# Sheet1.net
KiCad netlist of a schematic drawn in Altium Designer
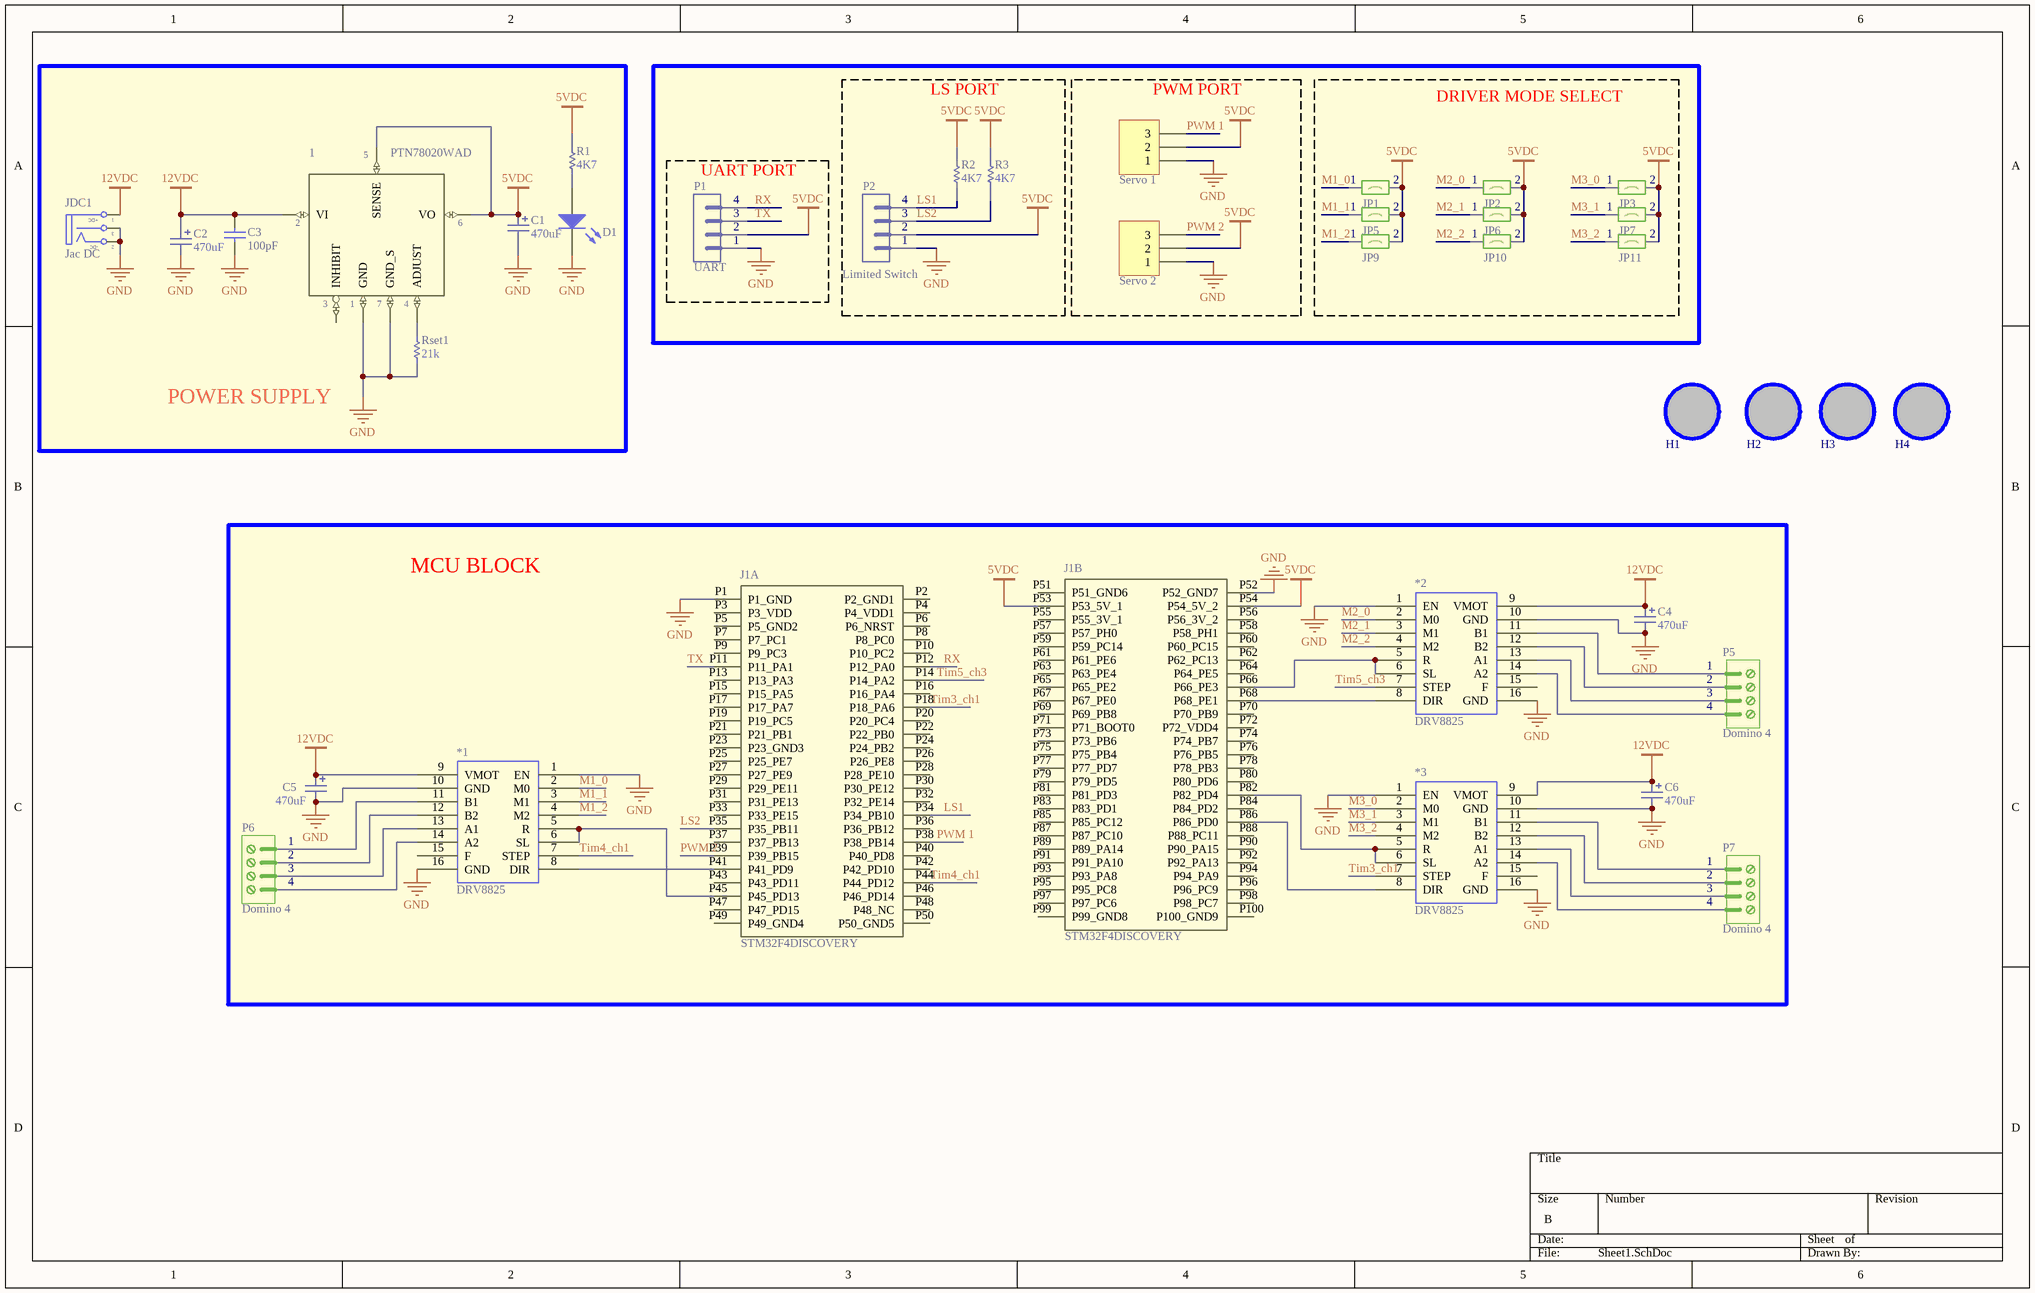
[diagram p0: Sheet1.SchDoc]

(export (version "E")
  (design (tool "Eeschema 10.0.6"))
  (components
    (comp (ref "*1") (value "DRV8825") (footprint "DRV8825") (libsource (lib "DRV8833") (part "DRV8825")))
    (comp (ref "*2") (value "DRV8825") (footprint "DRV8825") (libsource (lib "DRV8833") (part "DRV8825")))
    (comp (ref "*3") (value "DRV8825") (footprint "DRV8825") (libsource (lib "DRV8833") (part "DRV8825")))
    (comp (ref "1")
      (value "PTN78020WAD")
      (footprint "PTN78020WAD")
      (description "6-A Wide-Input Voltage Adjustable Switching egulator 7-Through-Hole Module -40 to 85")
      (fields (field (name "MF") "Texas Instruments"))
      (libsource (lib "PTN78020WAD") (part "PTN78020WAD"))
    )
    (comp (ref "C1")
      (value "470uF")
      (footprint "CP1/2.5")
      (description "Polarized Capacitor (Radial)")
      (fields (field (name "Comment") "Cap Pol"))
      (libsource (lib "minht57_lib") (part "Cap Pol"))
    )
    (comp (ref "C2")
      (value "470uF")
      (footprint "CP1.5/3.4")
      (description "Polarized Capacitor (Radial)")
      (fields (field (name "Comment") "Cap Pol"))
      (libsource (lib "minht57_lib") (part "Cap Pol"))
    )
    (comp (ref "C3")
      (value "100pF")
      (footprint "CAP-SM-0805")
      (description "Capacitor")
      (fields (field (name "Comment") "Cap Non-Pol SMD"))
      (libsource (lib "PIF_Library") (part "Cap Non-Pol SMD"))
    )
    (comp (ref "C4")
      (value "470uF")
      (footprint "CP1/2.5")
      (description "Polarized Capacitor (Radial)")
      (fields (field (name "Comment") "Cap Pol"))
      (libsource (lib "minht57_lib") (part "Cap Pol"))
    )
    (comp (ref "C5")
      (value "470uF")
      (footprint "CP1/2.5")
      (description "Polarized Capacitor (Radial)")
      (fields (field (name "Comment") "Cap Pol"))
      (libsource (lib "minht57_lib") (part "Cap Pol"))
    )
    (comp (ref "C6")
      (value "470uF")
      (footprint "CP1/2.5")
      (description "Polarized Capacitor (Radial)")
      (fields (field (name "Comment") "Cap Pol"))
      (libsource (lib "minht57_lib") (part "Cap Pol"))
    )
    (comp (ref "D1") (value "LED") (footprint "LED-3mm") (libsource (lib "PIF_Library") (part "LED")))
    (comp (ref "H1")
      (value "Hole")
      (footprint "LO KHOAN 3MM")
      (description "Hole 3mm")
      (libsource (lib "PIF_Library") (part "Hole"))
    )
    (comp (ref "H2")
      (value "Hole")
      (footprint "LO KHOAN 3MM")
      (description "Hole 3mm")
      (libsource (lib "PIF_Library") (part "Hole"))
    )
    (comp (ref "H3")
      (value "Hole")
      (footprint "LO KHOAN 3MM")
      (description "Hole 3mm")
      (libsource (lib "PIF_Library") (part "Hole"))
    )
    (comp (ref "H4")
      (value "Hole")
      (footprint "LO KHOAN 3MM")
      (description "Hole 3mm")
      (libsource (lib "PIF_Library") (part "Hole"))
    )
    (comp (ref "J1")
      (value "STM32F4DISCOVERY")
      (footprint "STMICROELECTRONICS_STM32F4DISCOVERY_STM32F4DISCOVERY(Primary)")
      (description "Development kit: ARM ST; pin strips, pin header; No.of")
      (fields (field (name "MF") "STMicroelectronics"))
      (libsource (lib "STM32F4DISCOVERY") (part "STM32F4DISCOVERY"))
    )
    (comp (ref "JDC1")
      (value "Jac DC")
      (footprint "DC-IN")
      (description "Jac DC input")
      (libsource (lib "syhaunguyen(1)") (part "DCIN"))
    )
    (comp (ref "JP1") (value "Jumper 2") (footprint "JP2") (libsource (lib "minht57_lib") (part "Jumper 2")))
    (comp (ref "JP2") (value "Jumper 2") (footprint "JP2") (libsource (lib "minht57_lib") (part "Jumper 2")))
    (comp (ref "JP3") (value "Jumper 2") (footprint "JP2") (libsource (lib "minht57_lib") (part "Jumper 2")))
    (comp (ref "JP5") (value "Jumper 2") (footprint "JP2") (libsource (lib "minht57_lib") (part "Jumper 2")))
    (comp (ref "JP6") (value "Jumper 2") (footprint "JP2") (libsource (lib "minht57_lib") (part "Jumper 2")))
    (comp (ref "JP7") (value "Jumper 2") (footprint "JP2") (libsource (lib "minht57_lib") (part "Jumper 2")))
    (comp (ref "JP9") (value "Jumper 2") (footprint "JP2") (libsource (lib "minht57_lib") (part "Jumper 2")))
    (comp (ref "JP10") (value "Jumper 2") (footprint "JP2") (libsource (lib "minht57_lib") (part "Jumper 2")))
    (comp (ref "JP11") (value "Jumper 2") (footprint "JP2") (libsource (lib "minht57_lib") (part "Jumper 2")))
    (comp (ref "P1")
      (value "UART")
      (footprint "JP4")
      (description "Header, 4-Pin")
      (fields (field (name "PUBLISHER") "Altium Limited"))
      (libsource (lib "minht57_lib") (part "Header 4"))
    )
    (comp (ref "P2")
      (value "Limited Switch")
      (footprint "JP4")
      (description "Header, 4-Pin")
      (fields (field (name "PUBLISHER") "Altium Limited"))
      (libsource (lib "minht57_lib") (part "Header 4"))
    )
    (comp (ref "P5")
      (value "Domino 4")
      (footprint "DOMINO 4 -5mm")
      (description "Domino 4-Pin")
      (fields (field (name "PUBLISHER") "Altium Limited"))
      (libsource (lib "minht57_lib") (part "Domino 4"))
    )
    (comp (ref "P6")
      (value "Domino 4")
      (footprint "DOMINO 4 -5mm")
      (description "Domino 4-Pin")
      (fields (field (name "PUBLISHER") "Altium Limited"))
      (libsource (lib "") (part "Domino 4_1"))
    )
    (comp (ref "P7")
      (value "Domino 4")
      (footprint "DOMINO 4 -5mm")
      (description "Domino 4-Pin")
      (fields (field (name "PUBLISHER") "Altium Limited"))
      (libsource (lib "minht57_lib") (part "Domino 4"))
    )
    (comp (ref "R1")
      (value "4K7")
      (footprint "RES-SM-0805")
      (description "Resistor")
      (fields (field (name "Comment") "Res SMD"))
      (libsource (lib "minht57_lib") (part "Res SMD"))
    )
    (comp (ref "R2")
      (value "4K7")
      (footprint "RES-SM-0805")
      (description "Resistor")
      (fields (field (name "Comment") "Res SMD"))
      (libsource (lib "minht57_lib") (part "Res SMD"))
    )
    (comp (ref "R3")
      (value "4K7")
      (footprint "RES-SM-0805")
      (description "Resistor")
      (fields (field (name "Comment") "Res SMD"))
      (libsource (lib "minht57_lib") (part "Res SMD"))
    )
    (comp (ref "Rset1")
      (value "Res SMD")
      (footprint "RES-SM-0805")
      (description "Resistor")
      (fields (field (name "1%") "21k"))
      (libsource (lib "minht57_lib") (part "Res SMD"))
    )
    (comp (ref "Servo 1")
      (value "Header 3")
      (footprint "JP3")
      (description "Header, 3-Pin")
      (fields (field (name "PUBLISHER") "Altium Limited"))
      (libsource (lib "PIF_Library") (part "Header 3"))
    )
    (comp (ref "Servo 2")
      (value "Header 3")
      (footprint "JP3")
      (description "Header, 3-Pin")
      (fields (field (name "PUBLISHER") "Altium Limited"))
      (libsource (lib "PIF_Library") (part "Header 3"))
    )
  )
  (nets
    (net (code "1") (name "/LS1") (class "Default")
      (node (ref "J1") (pin "P34") (pinfunction "P34_PB10_P34") (pintype "passive"))
      (node (ref "P2") (pin "4") (pinfunction "4_4") (pintype "passive"))
      (node (ref "R2") (pin "1") (pinfunction "1_1") (pintype "passive"))
    )
    (net (code "2") (name "/LS2") (class "Default")
      (node (ref "J1") (pin "P35") (pinfunction "P35_PB11_P35") (pintype "passive"))
      (node (ref "P2") (pin "3") (pinfunction "3_3") (pintype "passive"))
      (node (ref "R3") (pin "1") (pinfunction "1_1") (pintype "passive"))
    )
    (net (code "3") (name "/M1_0") (class "Default")
      (node (ref "*1") (pin "2") (pinfunction "M0_2") (pintype "passive"))
      (node (ref "JP1") (pin "1") (pinfunction "1_1") (pintype "passive"))
    )
    (net (code "4") (name "/M1_1") (class "Default")
      (node (ref "*1") (pin "3") (pinfunction "M1_3") (pintype "passive"))
      (node (ref "JP5") (pin "1") (pinfunction "1_1") (pintype "passive"))
    )
    (net (code "5") (name "/M1_2") (class "Default")
      (node (ref "*1") (pin "4") (pinfunction "M2_4") (pintype "passive"))
      (node (ref "JP9") (pin "1") (pinfunction "1_1") (pintype "passive"))
    )
    (net (code "6") (name "/M2_0") (class "Default")
      (node (ref "*2") (pin "2") (pinfunction "M0_2") (pintype "passive"))
      (node (ref "JP2") (pin "1") (pinfunction "1_1") (pintype "passive"))
    )
    (net (code "7") (name "/M2_1") (class "Default")
      (node (ref "*2") (pin "3") (pinfunction "M1_3") (pintype "passive"))
      (node (ref "JP6") (pin "1") (pinfunction "1_1") (pintype "passive"))
    )
    (net (code "8") (name "/M2_2") (class "Default")
      (node (ref "*2") (pin "4") (pinfunction "M2_4") (pintype "passive"))
      (node (ref "JP10") (pin "1") (pinfunction "1_1") (pintype "passive"))
    )
    (net (code "9") (name "/M3_0") (class "Default")
      (node (ref "*3") (pin "2") (pinfunction "M0_2") (pintype "passive"))
      (node (ref "JP3") (pin "1") (pinfunction "1_1") (pintype "passive"))
    )
    (net (code "10") (name "/M3_1") (class "Default")
      (node (ref "*3") (pin "3") (pinfunction "M1_3") (pintype "passive"))
      (node (ref "JP7") (pin "1") (pinfunction "1_1") (pintype "passive"))
    )
    (net (code "11") (name "/M3_2") (class "Default")
      (node (ref "*3") (pin "4") (pinfunction "M2_4") (pintype "passive"))
      (node (ref "JP11") (pin "1") (pinfunction "1_1") (pintype "passive"))
    )
    (net (code "12") (name "/PWM 1") (class "Default")
      (node (ref "J1") (pin "P38") (pinfunction "P38_PB14_P38") (pintype "passive"))
      (node (ref "Servo 1") (pin "3") (pinfunction "3_3") (pintype "passive"))
    )
    (net (code "13") (name "/PWM 2") (class "Default")
      (node (ref "J1") (pin "P39") (pinfunction "P39_PB15_P39") (pintype "passive"))
      (node (ref "Servo 2") (pin "3") (pinfunction "3_3") (pintype "passive"))
    )
    (net (code "14") (name "/RX") (class "Default")
      (node (ref "J1") (pin "P12") (pinfunction "P12_PA0_P12") (pintype "passive"))
      (node (ref "P1") (pin "4") (pinfunction "4_4") (pintype "passive"))
    )
    (net (code "15") (name "/TX") (class "Default")
      (node (ref "J1") (pin "P11") (pinfunction "P11_PA1_P11") (pintype "passive"))
      (node (ref "P1") (pin "3") (pinfunction "3_3") (pintype "passive"))
    )
    (net (code "16") (name "/Tim3_ch1") (class "Default")
      (node (ref "*3") (pin "7") (pinfunction "STEP_7") (pintype "passive"))
      (node (ref "J1") (pin "P18") (pinfunction "P18_PA6_P18") (pintype "passive"))
    )
    (net (code "17") (name "/Tim4_ch1") (class "Default")
      (node (ref "*1") (pin "7") (pinfunction "STEP_7") (pintype "passive"))
      (node (ref "J1") (pin "P44") (pinfunction "P44_PD12_P44") (pintype "passive"))
    )
    (net (code "18") (name "/Tim5_ch3") (class "Default")
      (node (ref "*2") (pin "7") (pinfunction "STEP_7") (pintype "passive"))
      (node (ref "J1") (pin "P14") (pinfunction "P14_PA2_P14") (pintype "passive"))
    )
    (net (code "19") (name "5VDC") (class "Default")
      (node (ref "1") (pin "5") (pinfunction "SENSE_5") (pintype "bidirectional"))
      (node (ref "1") (pin "6") (pinfunction "VO_6") (pintype "bidirectional"))
      (node (ref "C1") (pin "1") (pinfunction "1_1") (pintype "passive"))
      (node (ref "J1") (pin "P53") (pinfunction "P53_5V_1_P53") (pintype "passive"))
      (node (ref "J1") (pin "P54") (pinfunction "P54_5V_2_P54") (pintype "passive"))
      (node (ref "JP1") (pin "2") (pinfunction "2_2") (pintype "passive"))
      (node (ref "JP10") (pin "2") (pinfunction "2_2") (pintype "passive"))
      (node (ref "JP11") (pin "2") (pinfunction "2_2") (pintype "passive"))
      (node (ref "JP2") (pin "2") (pinfunction "2_2") (pintype "passive"))
      (node (ref "JP3") (pin "2") (pinfunction "2_2") (pintype "passive"))
      (node (ref "JP5") (pin "2") (pinfunction "2_2") (pintype "passive"))
      (node (ref "JP6") (pin "2") (pinfunction "2_2") (pintype "passive"))
      (node (ref "JP7") (pin "2") (pinfunction "2_2") (pintype "passive"))
      (node (ref "JP9") (pin "2") (pinfunction "2_2") (pintype "passive"))
      (node (ref "P1") (pin "2") (pinfunction "2_2") (pintype "passive"))
      (node (ref "P2") (pin "2") (pinfunction "2_2") (pintype "passive"))
      (node (ref "R1") (pin "2") (pinfunction "2_2") (pintype "passive"))
      (node (ref "R2") (pin "2") (pinfunction "2_2") (pintype "passive"))
      (node (ref "R3") (pin "2") (pinfunction "2_2") (pintype "passive"))
      (node (ref "Servo 1") (pin "2") (pinfunction "2_2") (pintype "passive"))
      (node (ref "Servo 2") (pin "2") (pinfunction "2_2") (pintype "passive"))
    )
    (net (code "20") (name "12VDC") (class "Default")
      (node (ref "*1") (pin "9") (pinfunction "VMOT_9") (pintype "passive"))
      (node (ref "*2") (pin "9") (pinfunction "VMOT_9") (pintype "passive"))
      (node (ref "*3") (pin "9") (pinfunction "VMOT_9") (pintype "passive"))
      (node (ref "1") (pin "2") (pinfunction "VI_2") (pintype "bidirectional"))
      (node (ref "C2") (pin "1") (pinfunction "1_1") (pintype "passive"))
      (node (ref "C3") (pin "2") (pinfunction "2_2") (pintype "passive"))
      (node (ref "C4") (pin "1") (pinfunction "1_1") (pintype "passive"))
      (node (ref "C5") (pin "1") (pinfunction "1_1") (pintype "passive"))
      (node (ref "C6") (pin "1") (pinfunction "1_1") (pintype "passive"))
      (node (ref "JDC1") (pin "1") (pinfunction "T_1") (pintype "passive"))
    )
    (net (code "21") (name "GND") (class "Default")
      (node (ref "*1") (pin "1") (pinfunction "EN_1") (pintype "passive"))
      (node (ref "*1") (pin "10") (pinfunction "GND_10") (pintype "passive"))
      (node (ref "*1") (pin "16") (pinfunction "GND_16") (pintype "passive"))
      (node (ref "*2") (pin "1") (pinfunction "EN_1") (pintype "passive"))
      (node (ref "*2") (pin "10") (pinfunction "GND_10") (pintype "passive"))
      (node (ref "*2") (pin "16") (pinfunction "GND_16") (pintype "passive"))
      (node (ref "*3") (pin "1") (pinfunction "EN_1") (pintype "passive"))
      (node (ref "*3") (pin "10") (pinfunction "GND_10") (pintype "passive"))
      (node (ref "*3") (pin "16") (pinfunction "GND_16") (pintype "passive"))
      (node (ref "1") (pin "1") (pinfunction "GND_1") (pintype "bidirectional"))
      (node (ref "1") (pin "7") (pinfunction "GND_S_7") (pintype "bidirectional"))
      (node (ref "C1") (pin "2") (pinfunction "2_2") (pintype "passive"))
      (node (ref "C2") (pin "2") (pinfunction "2_2") (pintype "passive"))
      (node (ref "C3") (pin "1") (pinfunction "1_1") (pintype "passive"))
      (node (ref "C4") (pin "2") (pinfunction "2_2") (pintype "passive"))
      (node (ref "C5") (pin "2") (pinfunction "2_2") (pintype "passive"))
      (node (ref "C6") (pin "2") (pinfunction "2_2") (pintype "passive"))
      (node (ref "D1") (pin "2") (pinfunction "K_2") (pintype "passive"))
      (node (ref "J1") (pin "P1") (pinfunction "P1_GND_P1") (pintype "passive"))
      (node (ref "J1") (pin "P52") (pinfunction "P52_GND7_P52") (pintype "passive"))
      (node (ref "JDC1") (pin "2") (pinfunction "TN_2") (pintype "passive"))
      (node (ref "JDC1") (pin "3") (pinfunction "S_3") (pintype "power_in"))
      (node (ref "P1") (pin "1") (pinfunction "1_1") (pintype "passive"))
      (node (ref "P2") (pin "1") (pinfunction "1_1") (pintype "passive"))
      (node (ref "Rset1") (pin "1") (pinfunction "1_1") (pintype "passive"))
      (node (ref "Servo 1") (pin "1") (pinfunction "1_1") (pintype "passive"))
      (node (ref "Servo 2") (pin "1") (pinfunction "1_1") (pintype "passive"))
    )
    (net (code "22") (name "Net-(*1-A1)") (class "Default")
      (node (ref "*1") (pin "13") (pinfunction "A1_13") (pintype "passive"))
      (node (ref "P6") (pin "3") (pinfunction "3_3") (pintype "passive"))
    )
    (net (code "23") (name "Net-(*1-A2)") (class "Default")
      (node (ref "*1") (pin "14") (pinfunction "A2_14") (pintype "passive"))
      (node (ref "P6") (pin "4") (pinfunction "4_4") (pintype "passive"))
    )
    (net (code "24") (name "Net-(*1-B1)") (class "Default")
      (node (ref "*1") (pin "11") (pinfunction "B1_11") (pintype "passive"))
      (node (ref "P6") (pin "1") (pinfunction "1_1") (pintype "passive"))
    )
    (net (code "25") (name "Net-(*1-B2)") (class "Default")
      (node (ref "*1") (pin "12") (pinfunction "B2_12") (pintype "passive"))
      (node (ref "P6") (pin "2") (pinfunction "2_2") (pintype "passive"))
    )
    (net (code "26") (name "Net-(*1-DIR)") (class "Default")
      (node (ref "*1") (pin "8") (pinfunction "DIR_8") (pintype "passive"))
      (node (ref "J1") (pin "P41") (pinfunction "P41_PD9_P41") (pintype "passive"))
    )
    (net (code "27") (name "Net-(*1-R)") (class "Default")
      (node (ref "*1") (pin "5") (pinfunction "R_5") (pintype "passive"))
      (node (ref "*1") (pin "6") (pinfunction "SL_6") (pintype "passive"))
      (node (ref "J1") (pin "P45") (pinfunction "P45_PD13_P45") (pintype "passive"))
    )
    (net (code "28") (name "Net-(*2-A1)") (class "Default")
      (node (ref "*2") (pin "13") (pinfunction "A1_13") (pintype "passive"))
      (node (ref "P5") (pin "3") (pinfunction "3_3") (pintype "passive"))
    )
    (net (code "29") (name "Net-(*2-A2)") (class "Default")
      (node (ref "*2") (pin "14") (pinfunction "A2_14") (pintype "passive"))
      (node (ref "P5") (pin "4") (pinfunction "4_4") (pintype "passive"))
    )
    (net (code "30") (name "Net-(*2-B1)") (class "Default")
      (node (ref "*2") (pin "11") (pinfunction "B1_11") (pintype "passive"))
      (node (ref "P5") (pin "1") (pinfunction "1_1") (pintype "passive"))
    )
    (net (code "31") (name "Net-(*2-B2)") (class "Default")
      (node (ref "*2") (pin "12") (pinfunction "B2_12") (pintype "passive"))
      (node (ref "P5") (pin "2") (pinfunction "2_2") (pintype "passive"))
    )
    (net (code "32") (name "Net-(*2-DIR)") (class "Default")
      (node (ref "*2") (pin "8") (pinfunction "DIR_8") (pintype "passive"))
      (node (ref "J1") (pin "P68") (pinfunction "P68_PE1_P68") (pintype "passive"))
    )
    (net (code "33") (name "Net-(*2-R)") (class "Default")
      (node (ref "*2") (pin "5") (pinfunction "R_5") (pintype "passive"))
      (node (ref "*2") (pin "6") (pinfunction "SL_6") (pintype "passive"))
      (node (ref "J1") (pin "P66") (pinfunction "P66_PE3_P66") (pintype "passive"))
    )
    (net (code "34") (name "Net-(*3-A1)") (class "Default")
      (node (ref "*3") (pin "13") (pinfunction "A1_13") (pintype "passive"))
      (node (ref "P7") (pin "3") (pinfunction "3_3") (pintype "passive"))
    )
    (net (code "35") (name "Net-(*3-A2)") (class "Default")
      (node (ref "*3") (pin "14") (pinfunction "A2_14") (pintype "passive"))
      (node (ref "P7") (pin "4") (pinfunction "4_4") (pintype "passive"))
    )
    (net (code "36") (name "Net-(*3-B1)") (class "Default")
      (node (ref "*3") (pin "11") (pinfunction "B1_11") (pintype "passive"))
      (node (ref "P7") (pin "1") (pinfunction "1_1") (pintype "passive"))
    )
    (net (code "37") (name "Net-(*3-B2)") (class "Default")
      (node (ref "*3") (pin "12") (pinfunction "B2_12") (pintype "passive"))
      (node (ref "P7") (pin "2") (pinfunction "2_2") (pintype "passive"))
    )
    (net (code "38") (name "Net-(*3-DIR)") (class "Default")
      (node (ref "*3") (pin "8") (pinfunction "DIR_8") (pintype "passive"))
      (node (ref "J1") (pin "P86") (pinfunction "P86_PD0_P86") (pintype "passive"))
    )
    (net (code "39") (name "Net-(*3-R)") (class "Default")
      (node (ref "*3") (pin "5") (pinfunction "R_5") (pintype "passive"))
      (node (ref "*3") (pin "6") (pinfunction "SL_6") (pintype "passive"))
      (node (ref "J1") (pin "P82") (pinfunction "P82_PD4_P82") (pintype "passive"))
    )
    (net (code "40") (name "Net-(1-ADJUST)") (class "Default")
      (node (ref "1") (pin "4") (pinfunction "ADJUST_4") (pintype "bidirectional"))
      (node (ref "Rset1") (pin "2") (pinfunction "2_2") (pintype "passive"))
    )
    (net (code "41") (name "Net-(D1-A)") (class "Default")
      (node (ref "D1") (pin "1") (pinfunction "A_1") (pintype "passive"))
      (node (ref "R1") (pin "1") (pinfunction "1_1") (pintype "passive"))
    )
    (net (code "42") (name "unconnected-(*1-F-Pad15)") (class "Default")
      (node (ref "*1") (pin "15") (pinfunction "F_15") (pintype "passive"))
    )
    (net (code "43") (name "unconnected-(*2-F-Pad15)") (class "Default")
      (node (ref "*2") (pin "15") (pinfunction "F_15") (pintype "passive"))
    )
    (net (code "44") (name "unconnected-(*3-F-Pad15)") (class "Default")
      (node (ref "*3") (pin "15") (pinfunction "F_15") (pintype "passive"))
    )
    (net (code "45") (name "unconnected-(1-INHIBIT-Pad3)") (class "Default")
      (node (ref "1") (pin "3") (pinfunction "INHIBIT_3") (pintype "bidirectional"))
    )
    (net (code "46") (name "unconnected-(H1-Pad1)") (class "Default")
      (node (ref "H1") (pin "1") (pinfunction "1_1") (pintype "passive"))
    )
    (net (code "47") (name "unconnected-(H2-Pad1)") (class "Default")
      (node (ref "H2") (pin "1") (pinfunction "1_1") (pintype "passive"))
    )
    (net (code "48") (name "unconnected-(H3-Pad1)") (class "Default")
      (node (ref "H3") (pin "1") (pinfunction "1_1") (pintype "passive"))
    )
    (net (code "49") (name "unconnected-(H4-Pad1)") (class "Default")
      (node (ref "H4") (pin "1") (pinfunction "1_1") (pintype "passive"))
    )
    (net (code "50") (name "unconnected-(J1A-P2_GND1-PadP2)") (class "Default")
      (node (ref "J1") (pin "P2") (pinfunction "P2_GND1_P2") (pintype "passive"))
    )
    (net (code "51") (name "unconnected-(J1A-P3_VDD-PadP3)") (class "Default")
      (node (ref "J1") (pin "P3") (pinfunction "P3_VDD_P3") (pintype "passive"))
    )
    (net (code "52") (name "unconnected-(J1A-P4_VDD1-PadP4)") (class "Default")
      (node (ref "J1") (pin "P4") (pinfunction "P4_VDD1_P4") (pintype "passive"))
    )
    (net (code "53") (name "unconnected-(J1A-P5_GND2-PadP5)") (class "Default")
      (node (ref "J1") (pin "P5") (pinfunction "P5_GND2_P5") (pintype "passive"))
    )
    (net (code "54") (name "unconnected-(J1A-P6_NRST-PadP6)") (class "Default")
      (node (ref "J1") (pin "P6") (pinfunction "P6_NRST_P6") (pintype "passive"))
    )
    (net (code "55") (name "unconnected-(J1A-P7_PC1-PadP7)") (class "Default")
      (node (ref "J1") (pin "P7") (pinfunction "P7_PC1_P7") (pintype "passive"))
    )
    (net (code "56") (name "unconnected-(J1A-P8_PC0-PadP8)") (class "Default")
      (node (ref "J1") (pin "P8") (pinfunction "P8_PC0_P8") (pintype "passive"))
    )
    (net (code "57") (name "unconnected-(J1A-P9_PC3-PadP9)") (class "Default")
      (node (ref "J1") (pin "P9") (pinfunction "P9_PC3_P9") (pintype "passive"))
    )
    (net (code "58") (name "unconnected-(J1A-P10_PC2-PadP10)") (class "Default")
      (node (ref "J1") (pin "P10") (pinfunction "P10_PC2_P10") (pintype "passive"))
    )
    (net (code "59") (name "unconnected-(J1A-P13_PA3-PadP13)") (class "Default")
      (node (ref "J1") (pin "P13") (pinfunction "P13_PA3_P13") (pintype "passive"))
    )
    (net (code "60") (name "unconnected-(J1A-P15_PA5-PadP15)") (class "Default")
      (node (ref "J1") (pin "P15") (pinfunction "P15_PA5_P15") (pintype "passive"))
    )
    (net (code "61") (name "unconnected-(J1A-P16_PA4-PadP16)") (class "Default")
      (node (ref "J1") (pin "P16") (pinfunction "P16_PA4_P16") (pintype "passive"))
    )
    (net (code "62") (name "unconnected-(J1A-P17_PA7-PadP17)") (class "Default")
      (node (ref "J1") (pin "P17") (pinfunction "P17_PA7_P17") (pintype "passive"))
    )
    (net (code "63") (name "unconnected-(J1A-P19_PC5-PadP19)") (class "Default")
      (node (ref "J1") (pin "P19") (pinfunction "P19_PC5_P19") (pintype "passive"))
    )
    (net (code "64") (name "unconnected-(J1A-P20_PC4-PadP20)") (class "Default")
      (node (ref "J1") (pin "P20") (pinfunction "P20_PC4_P20") (pintype "passive"))
    )
    (net (code "65") (name "unconnected-(J1A-P21_PB1-PadP21)") (class "Default")
      (node (ref "J1") (pin "P21") (pinfunction "P21_PB1_P21") (pintype "passive"))
    )
    (net (code "66") (name "unconnected-(J1A-P22_PB0-PadP22)") (class "Default")
      (node (ref "J1") (pin "P22") (pinfunction "P22_PB0_P22") (pintype "passive"))
    )
    (net (code "67") (name "unconnected-(J1A-P23_GND3-PadP23)") (class "Default")
      (node (ref "J1") (pin "P23") (pinfunction "P23_GND3_P23") (pintype "passive"))
    )
    (net (code "68") (name "unconnected-(J1A-P24_PB2-PadP24)") (class "Default")
      (node (ref "J1") (pin "P24") (pinfunction "P24_PB2_P24") (pintype "passive"))
    )
    (net (code "69") (name "unconnected-(J1A-P25_PE7-PadP25)") (class "Default")
      (node (ref "J1") (pin "P25") (pinfunction "P25_PE7_P25") (pintype "passive"))
    )
    (net (code "70") (name "unconnected-(J1A-P26_PE8-PadP26)") (class "Default")
      (node (ref "J1") (pin "P26") (pinfunction "P26_PE8_P26") (pintype "passive"))
    )
    (net (code "71") (name "unconnected-(J1A-P27_PE9-PadP27)") (class "Default")
      (node (ref "J1") (pin "P27") (pinfunction "P27_PE9_P27") (pintype "passive"))
    )
    (net (code "72") (name "unconnected-(J1A-P28_PE10-PadP28)") (class "Default")
      (node (ref "J1") (pin "P28") (pinfunction "P28_PE10_P28") (pintype "passive"))
    )
    (net (code "73") (name "unconnected-(J1A-P29_PE11-PadP29)") (class "Default")
      (node (ref "J1") (pin "P29") (pinfunction "P29_PE11_P29") (pintype "passive"))
    )
    (net (code "74") (name "unconnected-(J1A-P30_PE12-PadP30)") (class "Default")
      (node (ref "J1") (pin "P30") (pinfunction "P30_PE12_P30") (pintype "passive"))
    )
    (net (code "75") (name "unconnected-(J1A-P31_PE13-PadP31)") (class "Default")
      (node (ref "J1") (pin "P31") (pinfunction "P31_PE13_P31") (pintype "passive"))
    )
    (net (code "76") (name "unconnected-(J1A-P32_PE14-PadP32)") (class "Default")
      (node (ref "J1") (pin "P32") (pinfunction "P32_PE14_P32") (pintype "passive"))
    )
    (net (code "77") (name "unconnected-(J1A-P33_PE15-PadP33)") (class "Default")
      (node (ref "J1") (pin "P33") (pinfunction "P33_PE15_P33") (pintype "passive"))
    )
    (net (code "78") (name "unconnected-(J1A-P36_PB12-PadP36)") (class "Default")
      (node (ref "J1") (pin "P36") (pinfunction "P36_PB12_P36") (pintype "passive"))
    )
    (net (code "79") (name "unconnected-(J1A-P37_PB13-PadP37)") (class "Default")
      (node (ref "J1") (pin "P37") (pinfunction "P37_PB13_P37") (pintype "passive"))
    )
    (net (code "80") (name "unconnected-(J1A-P40_PD8-PadP40)") (class "Default")
      (node (ref "J1") (pin "P40") (pinfunction "P40_PD8_P40") (pintype "passive"))
    )
    (net (code "81") (name "unconnected-(J1A-P42_PD10-PadP42)") (class "Default")
      (node (ref "J1") (pin "P42") (pinfunction "P42_PD10_P42") (pintype "passive"))
    )
    (net (code "82") (name "unconnected-(J1A-P43_PD11-PadP43)") (class "Default")
      (node (ref "J1") (pin "P43") (pinfunction "P43_PD11_P43") (pintype "passive"))
    )
    (net (code "83") (name "unconnected-(J1A-P46_PD14-PadP46)") (class "Default")
      (node (ref "J1") (pin "P46") (pinfunction "P46_PD14_P46") (pintype "passive"))
    )
    (net (code "84") (name "unconnected-(J1A-P47_PD15-PadP47)") (class "Default")
      (node (ref "J1") (pin "P47") (pinfunction "P47_PD15_P47") (pintype "passive"))
    )
    (net (code "85") (name "unconnected-(J1A-P48_NC-PadP48)") (class "Default")
      (node (ref "J1") (pin "P48") (pinfunction "P48_NC_P48") (pintype "passive"))
    )
    (net (code "86") (name "unconnected-(J1A-P49_GND4-PadP49)") (class "Default")
      (node (ref "J1") (pin "P49") (pinfunction "P49_GND4_P49") (pintype "passive"))
    )
    (net (code "87") (name "unconnected-(J1A-P50_GND5-PadP50)") (class "Default")
      (node (ref "J1") (pin "P50") (pinfunction "P50_GND5_P50") (pintype "passive"))
    )
    (net (code "88") (name "unconnected-(J1B-P51_GND6-PadP51)") (class "Default")
      (node (ref "J1") (pin "P51") (pinfunction "P51_GND6_P51") (pintype "passive"))
    )
    (net (code "89") (name "unconnected-(J1B-P55_3V_1-PadP55)") (class "Default")
      (node (ref "J1") (pin "P55") (pinfunction "P55_3V_1_P55") (pintype "passive"))
    )
    (net (code "90") (name "unconnected-(J1B-P56_3V_2-PadP56)") (class "Default")
      (node (ref "J1") (pin "P56") (pinfunction "P56_3V_2_P56") (pintype "passive"))
    )
    (net (code "91") (name "unconnected-(J1B-P57_PH0-PadP57)") (class "Default")
      (node (ref "J1") (pin "P57") (pinfunction "P57_PH0_P57") (pintype "passive"))
    )
    (net (code "92") (name "unconnected-(J1B-P58_PH1-PadP58)") (class "Default")
      (node (ref "J1") (pin "P58") (pinfunction "P58_PH1_P58") (pintype "passive"))
    )
    (net (code "93") (name "unconnected-(J1B-P59_PC14-PadP59)") (class "Default")
      (node (ref "J1") (pin "P59") (pinfunction "P59_PC14_P59") (pintype "passive"))
    )
    (net (code "94") (name "unconnected-(J1B-P60_PC15-PadP60)") (class "Default")
      (node (ref "J1") (pin "P60") (pinfunction "P60_PC15_P60") (pintype "passive"))
    )
    (net (code "95") (name "unconnected-(J1B-P61_PE6-PadP61)") (class "Default")
      (node (ref "J1") (pin "P61") (pinfunction "P61_PE6_P61") (pintype "passive"))
    )
    (net (code "96") (name "unconnected-(J1B-P62_PC13-PadP62)") (class "Default")
      (node (ref "J1") (pin "P62") (pinfunction "P62_PC13_P62") (pintype "passive"))
    )
    (net (code "97") (name "unconnected-(J1B-P63_PE4-PadP63)") (class "Default")
      (node (ref "J1") (pin "P63") (pinfunction "P63_PE4_P63") (pintype "passive"))
    )
    (net (code "98") (name "unconnected-(J1B-P64_PE5-PadP64)") (class "Default")
      (node (ref "J1") (pin "P64") (pinfunction "P64_PE5_P64") (pintype "passive"))
    )
    (net (code "99") (name "unconnected-(J1B-P65_PE2-PadP65)") (class "Default")
      (node (ref "J1") (pin "P65") (pinfunction "P65_PE2_P65") (pintype "passive"))
    )
    (net (code "100") (name "unconnected-(J1B-P67_PE0-PadP67)") (class "Default")
      (node (ref "J1") (pin "P67") (pinfunction "P67_PE0_P67") (pintype "passive"))
    )
    (net (code "101") (name "unconnected-(J1B-P69_PB8-PadP69)") (class "Default")
      (node (ref "J1") (pin "P69") (pinfunction "P69_PB8_P69") (pintype "passive"))
    )
    (net (code "102") (name "unconnected-(J1B-P70_PB9-PadP70)") (class "Default")
      (node (ref "J1") (pin "P70") (pinfunction "P70_PB9_P70") (pintype "passive"))
    )
    (net (code "103") (name "unconnected-(J1B-P71_BOOT0-PadP71)") (class "Default")
      (node (ref "J1") (pin "P71") (pinfunction "P71_BOOT0_P71") (pintype "passive"))
    )
    (net (code "104") (name "unconnected-(J1B-P72_VDD4-PadP72)") (class "Default")
      (node (ref "J1") (pin "P72") (pinfunction "P72_VDD4_P72") (pintype "passive"))
    )
    (net (code "105") (name "unconnected-(J1B-P73_PB6-PadP73)") (class "Default")
      (node (ref "J1") (pin "P73") (pinfunction "P73_PB6_P73") (pintype "passive"))
    )
    (net (code "106") (name "unconnected-(J1B-P74_PB7-PadP74)") (class "Default")
      (node (ref "J1") (pin "P74") (pinfunction "P74_PB7_P74") (pintype "passive"))
    )
    (net (code "107") (name "unconnected-(J1B-P75_PB4-PadP75)") (class "Default")
      (node (ref "J1") (pin "P75") (pinfunction "P75_PB4_P75") (pintype "passive"))
    )
    (net (code "108") (name "unconnected-(J1B-P76_PB5-PadP76)") (class "Default")
      (node (ref "J1") (pin "P76") (pinfunction "P76_PB5_P76") (pintype "passive"))
    )
    (net (code "109") (name "unconnected-(J1B-P77_PD7-PadP77)") (class "Default")
      (node (ref "J1") (pin "P77") (pinfunction "P77_PD7_P77") (pintype "passive"))
    )
    (net (code "110") (name "unconnected-(J1B-P78_PB3-PadP78)") (class "Default")
      (node (ref "J1") (pin "P78") (pinfunction "P78_PB3_P78") (pintype "passive"))
    )
    (net (code "111") (name "unconnected-(J1B-P79_PD5-PadP79)") (class "Default")
      (node (ref "J1") (pin "P79") (pinfunction "P79_PD5_P79") (pintype "passive"))
    )
    (net (code "112") (name "unconnected-(J1B-P80_PD6-PadP80)") (class "Default")
      (node (ref "J1") (pin "P80") (pinfunction "P80_PD6_P80") (pintype "passive"))
    )
    (net (code "113") (name "unconnected-(J1B-P81_PD3-PadP81)") (class "Default")
      (node (ref "J1") (pin "P81") (pinfunction "P81_PD3_P81") (pintype "passive"))
    )
    (net (code "114") (name "unconnected-(J1B-P83_PD1-PadP83)") (class "Default")
      (node (ref "J1") (pin "P83") (pinfunction "P83_PD1_P83") (pintype "passive"))
    )
    (net (code "115") (name "unconnected-(J1B-P84_PD2-PadP84)") (class "Default")
      (node (ref "J1") (pin "P84") (pinfunction "P84_PD2_P84") (pintype "passive"))
    )
    (net (code "116") (name "unconnected-(J1B-P85_PC12-PadP85)") (class "Default")
      (node (ref "J1") (pin "P85") (pinfunction "P85_PC12_P85") (pintype "passive"))
    )
    (net (code "117") (name "unconnected-(J1B-P87_PC10-PadP87)") (class "Default")
      (node (ref "J1") (pin "P87") (pinfunction "P87_PC10_P87") (pintype "passive"))
    )
    (net (code "118") (name "unconnected-(J1B-P88_PC11-PadP88)") (class "Default")
      (node (ref "J1") (pin "P88") (pinfunction "P88_PC11_P88") (pintype "passive"))
    )
    (net (code "119") (name "unconnected-(J1B-P89_PA14-PadP89)") (class "Default")
      (node (ref "J1") (pin "P89") (pinfunction "P89_PA14_P89") (pintype "passive"))
    )
    (net (code "120") (name "unconnected-(J1B-P90_PA15-PadP90)") (class "Default")
      (node (ref "J1") (pin "P90") (pinfunction "P90_PA15_P90") (pintype "passive"))
    )
    (net (code "121") (name "unconnected-(J1B-P91_PA10-PadP91)") (class "Default")
      (node (ref "J1") (pin "P91") (pinfunction "P91_PA10_P91") (pintype "passive"))
    )
    (net (code "122") (name "unconnected-(J1B-P92_PA13-PadP92)") (class "Default")
      (node (ref "J1") (pin "P92") (pinfunction "P92_PA13_P92") (pintype "passive"))
    )
    (net (code "123") (name "unconnected-(J1B-P93_PA8-PadP93)") (class "Default")
      (node (ref "J1") (pin "P93") (pinfunction "P93_PA8_P93") (pintype "passive"))
    )
    (net (code "124") (name "unconnected-(J1B-P94_PA9-PadP94)") (class "Default")
      (node (ref "J1") (pin "P94") (pinfunction "P94_PA9_P94") (pintype "passive"))
    )
    (net (code "125") (name "unconnected-(J1B-P95_PC8-PadP95)") (class "Default")
      (node (ref "J1") (pin "P95") (pinfunction "P95_PC8_P95") (pintype "passive"))
    )
    (net (code "126") (name "unconnected-(J1B-P96_PC9-PadP96)") (class "Default")
      (node (ref "J1") (pin "P96") (pinfunction "P96_PC9_P96") (pintype "passive"))
    )
    (net (code "127") (name "unconnected-(J1B-P97_PC6-PadP97)") (class "Default")
      (node (ref "J1") (pin "P97") (pinfunction "P97_PC6_P97") (pintype "passive"))
    )
    (net (code "128") (name "unconnected-(J1B-P98_PC7-PadP98)") (class "Default")
      (node (ref "J1") (pin "P98") (pinfunction "P98_PC7_P98") (pintype "passive"))
    )
    (net (code "129") (name "unconnected-(J1B-P99_GND8-PadP99)") (class "Default")
      (node (ref "J1") (pin "P99") (pinfunction "P99_GND8_P99") (pintype "passive"))
    )
    (net (code "130") (name "unconnected-(J1B-P100_GND9-PadP100)") (class "Default")
      (node (ref "J1") (pin "P100") (pinfunction "P100_GND9_P100") (pintype "passive"))
    )
  )
)
